# ZENER.net
KiCad netlist of a schematic drawn in Altium Designer
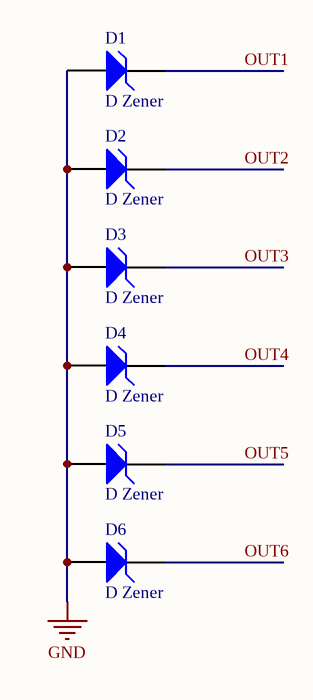
[diagram p0: ZENER.SchDoc]

(export (version "E")
  (design (tool "Eeschema 10.0.6"))
  (components
    (comp (ref "D1")
      (value "D Zener")
      (footprint "C1206")
      (description "Zener Diode")
      (fields (field (name "PUBLISHER") "Altium Limited"))
      (libsource (lib "Miscellaneous Devices") (part "D Zener"))
    )
    (comp (ref "D2")
      (value "D Zener")
      (footprint "C1206")
      (description "Zener Diode")
      (fields (field (name "PUBLISHER") "Altium Limited"))
      (libsource (lib "Miscellaneous Devices") (part "D Zener"))
    )
    (comp (ref "D3")
      (value "D Zener")
      (footprint "C1206")
      (description "Zener Diode")
      (fields (field (name "PUBLISHER") "Altium Limited"))
      (libsource (lib "Miscellaneous Devices") (part "D Zener"))
    )
    (comp (ref "D4")
      (value "D Zener")
      (footprint "C1206")
      (description "Zener Diode")
      (fields (field (name "PUBLISHER") "Altium Limited"))
      (libsource (lib "Miscellaneous Devices") (part "D Zener"))
    )
    (comp (ref "D5")
      (value "D Zener")
      (footprint "C1206")
      (description "Zener Diode")
      (fields (field (name "PUBLISHER") "Altium Limited"))
      (libsource (lib "Miscellaneous Devices") (part "D Zener"))
    )
    (comp (ref "D6")
      (value "D Zener")
      (footprint "C1206")
      (description "Zener Diode")
      (fields (field (name "PUBLISHER") "Altium Limited"))
      (libsource (lib "Miscellaneous Devices") (part "D Zener"))
    )
  )
  (nets
    (net (code "1") (name "/OUT1") (class "Default")
      (node (ref "D1") (pin "2") (pinfunction "K_2") (pintype "passive"))
    )
    (net (code "2") (name "/OUT2") (class "Default")
      (node (ref "D2") (pin "2") (pinfunction "K_2") (pintype "passive"))
    )
    (net (code "3") (name "/OUT3") (class "Default")
      (node (ref "D3") (pin "2") (pinfunction "K_2") (pintype "passive"))
    )
    (net (code "4") (name "/OUT4") (class "Default")
      (node (ref "D4") (pin "2") (pinfunction "K_2") (pintype "passive"))
    )
    (net (code "5") (name "/OUT5") (class "Default")
      (node (ref "D5") (pin "2") (pinfunction "K_2") (pintype "passive"))
    )
    (net (code "6") (name "/OUT6") (class "Default")
      (node (ref "D6") (pin "2") (pinfunction "K_2") (pintype "passive"))
    )
    (net (code "7") (name "GND") (class "Default")
      (node (ref "D1") (pin "1") (pinfunction "A_1") (pintype "passive"))
      (node (ref "D2") (pin "1") (pinfunction "A_1") (pintype "passive"))
      (node (ref "D3") (pin "1") (pinfunction "A_1") (pintype "passive"))
      (node (ref "D4") (pin "1") (pinfunction "A_1") (pintype "passive"))
      (node (ref "D5") (pin "1") (pinfunction "A_1") (pintype "passive"))
      (node (ref "D6") (pin "1") (pinfunction "A_1") (pintype "passive"))
    )
  )
)
